# POVBase.net
KiCad netlist of a schematic drawn in EAGLE
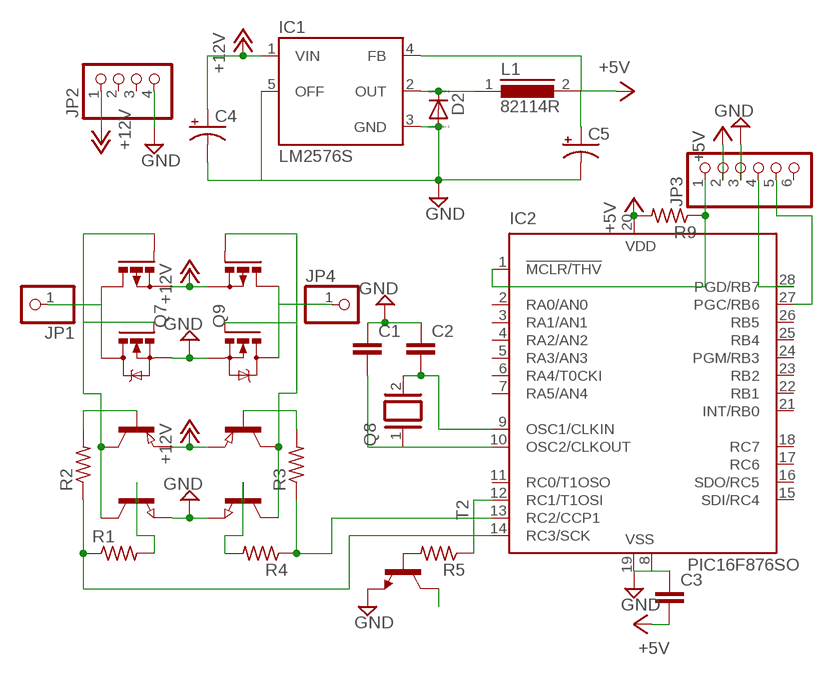
[diagram p0: schematic, sheet 1]

(export (version "E")
  (design (tool "Eeschema 10.0.6"))
  (components
    (comp (ref "C1")
      (value "C-EUC0805")
      (footprint "eagle-import:C0805")
      (libsource (lib "eagle-import") (part "C-EUC0805"))
    )
    (comp (ref "C2")
      (value "C-EUC0805")
      (footprint "eagle-import:C0805")
      (libsource (lib "eagle-import") (part "C-EUC0805"))
    )
    (comp (ref "C3")
      (value "C-EUC0805")
      (footprint "eagle-import:C0805")
      (libsource (lib "eagle-import") (part "C-EUC0805"))
    )
    (comp (ref "C4")
      (value "CPOL-USE2.5-7")
      (footprint "eagle-import:E2,5-7")
      (libsource (lib "eagle-import") (part "CPOL-USE2.5-7"))
    )
    (comp (ref "C5")
      (value "CPOL-USE1.8-4")
      (footprint "eagle-import:E1,8-4")
      (libsource (lib "eagle-import") (part "CPOL-USE1.8-4"))
    )
    (comp (ref "D2")
      (value "DIODE_E-SMC")
      (footprint "eagle-import:DIODE_SMC")
      (libsource (lib "eagle-import") (part "DIODE_E-SMC"))
    )
    (comp (ref "IC1")
      (value "LM2576S")
      (footprint "eagle-import:TO263-5")
      (libsource (lib "eagle-import") (part "LM2576S"))
    )
    (comp (ref "IC2")
      (value "PIC16F876SO")
      (footprint "eagle-import:SO28W")
      (fields (field (name "MF") "MICROCHIP") (field (name "MPN") "PIC16F876-20/SO"))
      (libsource (lib "eagle-import") (part "PIC16876SOF"))
    )
    (comp (ref "JP1")
      (value "PINHD-1X1")
      (footprint "eagle-import:1X01")
      (libsource (lib "eagle-import") (part "PINHD-1X1"))
    )
    (comp (ref "JP2")
      (value "PINHD-1X4")
      (footprint "eagle-import:1X04")
      (libsource (lib "eagle-import") (part "PINHD-1X4"))
    )
    (comp (ref "JP3")
      (value "PINHD-1X6")
      (footprint "eagle-import:1X06")
      (libsource (lib "eagle-import") (part "PINHD-1X6"))
    )
    (comp (ref "JP4")
      (value "PINHD-1X1")
      (footprint "eagle-import:1X01")
      (libsource (lib "eagle-import") (part "PINHD-1X1"))
    )
    (comp (ref "L1")
      (value "82114R")
      (footprint "eagle-import:82114R")
      (libsource (lib "eagle-import") (part "82114R"))
    )
    (comp (ref "Q1")
      (value "NPN-TRANSISTOR_SOT23")
      (footprint "eagle-import:SOT23")
      (libsource (lib "eagle-import") (part "NPN-TRANSISTOR_SOT23"))
    )
    (comp (ref "Q2")
      (value "NPN-TRANSISTOR_SOT23")
      (footprint "eagle-import:SOT23")
      (libsource (lib "eagle-import") (part "NPN-TRANSISTOR_SOT23"))
    )
    (comp (ref "Q3")
      (value "PNP-TRANSISTOR_SOT23")
      (footprint "eagle-import:SOT23")
      (libsource (lib "eagle-import") (part "PNP-TRANSISTOR_SOT23"))
    )
    (comp (ref "Q4")
      (value "PNP-TRANSISTOR_SOT23")
      (footprint "eagle-import:SOT23")
      (libsource (lib "eagle-import") (part "PNP-TRANSISTOR_SOT23"))
    )
    (comp (ref "Q5")
      (value "IRF540")
      (footprint "eagle-import:TO220BV")
      (libsource (lib "eagle-import") (part "IRF540"))
    )
    (comp (ref "Q6")
      (value "IRF540")
      (footprint "eagle-import:TO220BV")
      (libsource (lib "eagle-import") (part "IRF540"))
    )
    (comp (ref "Q7")
      (value "PMOSFET_PTO220BV")
      (footprint "eagle-import:TO220BV")
      (libsource (lib "eagle-import") (part "PMOSFET_PTO220BV"))
    )
    (comp (ref "Q8")
      (value "XTAL/S")
      (footprint "eagle-import:QS")
      (libsource (lib "eagle-import") (part "XTAL/S"))
    )
    (comp (ref "Q9")
      (value "PMOSFET_PTO220BV")
      (footprint "eagle-import:TO220BV")
      (libsource (lib "eagle-import") (part "PMOSFET_PTO220BV"))
    )
    (comp (ref "R1")
      (value "R-US_R0805")
      (footprint "eagle-import:R0805")
      (libsource (lib "eagle-import") (part "R-US_R0805"))
    )
    (comp (ref "R2")
      (value "R-US_R0805")
      (footprint "eagle-import:R0805")
      (libsource (lib "eagle-import") (part "R-US_R0805"))
    )
    (comp (ref "R3")
      (value "R-US_R0805")
      (footprint "eagle-import:R0805")
      (libsource (lib "eagle-import") (part "R-US_R0805"))
    )
    (comp (ref "R4")
      (value "R-US_R0805")
      (footprint "eagle-import:R0805")
      (libsource (lib "eagle-import") (part "R-US_R0805"))
    )
    (comp (ref "R5")
      (value "R-US_R0805")
      (footprint "eagle-import:R0805")
      (libsource (lib "eagle-import") (part "R-US_R0805"))
    )
    (comp (ref "R9")
      (value "R-US_R0805")
      (footprint "eagle-import:R0805")
      (libsource (lib "eagle-import") (part "R-US_R0805"))
    )
    (comp (ref "T2")
      (value "2SC1306")
      (footprint "eagle-import:TO220BV")
      (libsource (lib "eagle-import") (part "2SC1306"))
    )
  )
  (nets
    (net (code "1") (name "+5V") (class "Default")
      (node (ref "C3") (pin "2") (pinfunction "2_2") (pintype "passive"))
      (node (ref "C5") (pin "+") (pinfunction "+_+") (pintype "passive"))
      (node (ref "IC1") (pin "4") (pinfunction "FB_4") (pintype "input"))
      (node (ref "IC2") (pin "20") (pinfunction "VDD_20") (pintype "power_in"))
      (node (ref "JP3") (pin "2") (pinfunction "2_2") (pintype "passive"))
      (node (ref "L1") (pin "2") (pinfunction "2_2") (pintype "passive"))
      (node (ref "R9") (pin "2") (pinfunction "2_2") (pintype "passive"))
    )
    (net (code "2") (name "+12V") (class "Default")
      (node (ref "C4") (pin "+") (pinfunction "+_+") (pintype "passive"))
      (node (ref "IC1") (pin "1") (pinfunction "VIN_1") (pintype "power_in"))
      (node (ref "JP2") (pin "1") (pinfunction "1_1") (pintype "passive"))
      (node (ref "Q3") (pin "2") (pinfunction "E_2") (pintype "passive"))
      (node (ref "Q4") (pin "2") (pinfunction "E_2") (pintype "passive"))
      (node (ref "Q7") (pin "S") (pinfunction "S_S") (pintype "passive"))
      (node (ref "Q9") (pin "S") (pinfunction "S_S") (pintype "passive"))
    )
    (net (code "3") (name "GND") (class "Default")
      (node (ref "C1") (pin "1") (pinfunction "1_1") (pintype "passive"))
      (node (ref "C2") (pin "1") (pinfunction "1_1") (pintype "passive"))
      (node (ref "C3") (pin "1") (pinfunction "1_1") (pintype "passive"))
      (node (ref "C4") (pin "-") (pinfunction "-_-") (pintype "passive"))
      (node (ref "C5") (pin "-") (pinfunction "-_-") (pintype "passive"))
      (node (ref "D2") (pin "A") (pinfunction "C_A") (pintype "passive"))
      (node (ref "IC1") (pin "3") (pinfunction "GND_3") (pintype "power_in"))
      (node (ref "IC1") (pin "5") (pinfunction "OFF_5") (pintype "input"))
      (node (ref "IC2") (pin "19") (pinfunction "VSS_19") (pintype "power_in"))
      (node (ref "IC2") (pin "8") (pinfunction "VSS_8") (pintype "power_in"))
      (node (ref "JP2") (pin "4") (pinfunction "4_4") (pintype "passive"))
      (node (ref "JP3") (pin "3") (pinfunction "3_3") (pintype "passive"))
      (node (ref "Q1") (pin "2") (pinfunction "E_2") (pintype "passive"))
      (node (ref "Q2") (pin "2") (pinfunction "E_2") (pintype "passive"))
      (node (ref "Q5") (pin "S") (pinfunction "S_S") (pintype "passive"))
      (node (ref "Q6") (pin "S") (pinfunction "S_S") (pintype "passive"))
      (node (ref "T2") (pin "3") (pinfunction "E_3") (pintype "passive"))
    )
    (net (code "4") (name "Net-(D2-A)") (class "Default")
      (node (ref "D2") (pin "C") (pinfunction "A_C") (pintype "passive"))
      (node (ref "IC1") (pin "2") (pinfunction "OUT_2") (pintype "output"))
      (node (ref "L1") (pin "1") (pinfunction "1_1") (pintype "passive"))
    )
    (net (code "5") (name "Net-(IC2-OSC1{slash}CLKIN)") (class "Default")
      (node (ref "C2") (pin "2") (pinfunction "2_2") (pintype "passive"))
      (node (ref "IC2") (pin "9") (pinfunction "OSC1/CLKIN_9") (pintype "input"))
      (node (ref "Q8") (pin "2") (pinfunction "2_2") (pintype "passive"))
    )
    (net (code "6") (name "Net-(IC2-OSC2{slash}CLKOUT)") (class "Default")
      (node (ref "C1") (pin "2") (pinfunction "2_2") (pintype "passive"))
      (node (ref "IC2") (pin "10") (pinfunction "OSC2/CLKOUT_10") (pintype "output"))
      (node (ref "Q8") (pin "1") (pinfunction "1_1") (pintype "passive"))
    )
    (net (code "7") (name "Net-(IC2-PGC{slash}RB6)") (class "Default")
      (node (ref "IC2") (pin "27") (pinfunction "PGC/RB6_27") (pintype "bidirectional"))
      (node (ref "JP3") (pin "5") (pinfunction "5_5") (pintype "passive"))
    )
    (net (code "8") (name "Net-(IC2-PGD{slash}RB7)") (class "Default")
      (node (ref "IC2") (pin "28") (pinfunction "PGD/RB7_28") (pintype "bidirectional"))
      (node (ref "JP3") (pin "4") (pinfunction "4_4") (pintype "passive"))
    )
    (net (code "9") (name "Net-(IC2-RC1{slash}T1OSI)") (class "Default")
      (node (ref "IC2") (pin "12") (pinfunction "RC1/T1OSI_12") (pintype "bidirectional"))
      (node (ref "R5") (pin "1") (pinfunction "1_1") (pintype "passive"))
    )
    (net (code "10") (name "Net-(IC2-RC2{slash}CCP1)") (class "Default")
      (node (ref "IC2") (pin "13") (pinfunction "RC2/CCP1_13") (pintype "bidirectional"))
      (node (ref "R3") (pin "1") (pinfunction "1_1") (pintype "passive"))
      (node (ref "R4") (pin "1") (pinfunction "1_1") (pintype "passive"))
    )
    (net (code "11") (name "Net-(IC2-RC3{slash}SCK)") (class "Default")
      (node (ref "IC2") (pin "14") (pinfunction "RC3/SCK_14") (pintype "bidirectional"))
      (node (ref "R1") (pin "1") (pinfunction "1_1") (pintype "passive"))
      (node (ref "R2") (pin "1") (pinfunction "1_1") (pintype "passive"))
    )
    (net (code "12") (name "Net-(IC2-~{MCLR{slash}THV})") (class "Default")
      (node (ref "IC2") (pin "1") (pinfunction "~{MCLR/THV}_1") (pintype "input"))
      (node (ref "JP3") (pin "1") (pinfunction "1_1") (pintype "passive"))
      (node (ref "R9") (pin "1") (pinfunction "1_1") (pintype "passive"))
    )
    (net (code "13") (name "Net-(JP1-Pad1)") (class "Default")
      (node (ref "JP1") (pin "1") (pinfunction "1_1") (pintype "passive"))
      (node (ref "Q5") (pin "D") (pinfunction "D_D") (pintype "passive"))
      (node (ref "Q7") (pin "D") (pinfunction "D_D") (pintype "passive"))
    )
    (net (code "14") (name "Net-(JP4-Pad1)") (class "Default")
      (node (ref "JP4") (pin "1") (pinfunction "1_1") (pintype "passive"))
      (node (ref "Q6") (pin "D") (pinfunction "D_D") (pintype "passive"))
      (node (ref "Q9") (pin "D") (pinfunction "D_D") (pintype "passive"))
    )
    (net (code "15") (name "Net-(Q1-B)") (class "Default")
      (node (ref "Q1") (pin "1") (pinfunction "B_1") (pintype "passive"))
      (node (ref "R1") (pin "2") (pinfunction "2_2") (pintype "passive"))
    )
    (net (code "16") (name "Net-(Q1-C)") (class "Default")
      (node (ref "Q1") (pin "3") (pinfunction "C_3") (pintype "passive"))
      (node (ref "Q3") (pin "3") (pinfunction "C_3") (pintype "passive"))
      (node (ref "Q5") (pin "G") (pinfunction "G_G") (pintype "passive"))
      (node (ref "Q7") (pin "G") (pinfunction "G_G") (pintype "passive"))
    )
    (net (code "17") (name "Net-(Q2-B)") (class "Default")
      (node (ref "Q2") (pin "1") (pinfunction "B_1") (pintype "passive"))
      (node (ref "R4") (pin "2") (pinfunction "2_2") (pintype "passive"))
    )
    (net (code "18") (name "Net-(Q2-C)") (class "Default")
      (node (ref "Q2") (pin "3") (pinfunction "C_3") (pintype "passive"))
      (node (ref "Q4") (pin "3") (pinfunction "C_3") (pintype "passive"))
      (node (ref "Q6") (pin "G") (pinfunction "G_G") (pintype "passive"))
      (node (ref "Q9") (pin "G") (pinfunction "G_G") (pintype "passive"))
    )
    (net (code "19") (name "Net-(Q3-B)") (class "Default")
      (node (ref "Q3") (pin "1") (pinfunction "B_1") (pintype "passive"))
      (node (ref "R2") (pin "2") (pinfunction "2_2") (pintype "passive"))
    )
    (net (code "20") (name "Net-(Q4-B)") (class "Default")
      (node (ref "Q4") (pin "1") (pinfunction "B_1") (pintype "passive"))
      (node (ref "R3") (pin "2") (pinfunction "2_2") (pintype "passive"))
    )
    (net (code "21") (name "Net-(T2-B)") (class "Default")
      (node (ref "R5") (pin "2") (pinfunction "2_2") (pintype "passive"))
      (node (ref "T2") (pin "1") (pinfunction "B_1") (pintype "passive"))
    )
    (net (code "22") (name "unconnected-(IC2-INT{slash}RB0-Pad21)") (class "Default")
      (node (ref "IC2") (pin "21") (pinfunction "INT/RB0_21") (pintype "bidirectional"))
    )
    (net (code "23") (name "unconnected-(IC2-PGM{slash}RB3-Pad24)") (class "Default")
      (node (ref "IC2") (pin "24") (pinfunction "PGM/RB3_24") (pintype "bidirectional"))
    )
    (net (code "24") (name "unconnected-(IC2-RA0{slash}AN0-Pad2)") (class "Default")
      (node (ref "IC2") (pin "2") (pinfunction "RA0/AN0_2") (pintype "bidirectional"))
    )
    (net (code "25") (name "unconnected-(IC2-RA1{slash}AN1-Pad3)") (class "Default")
      (node (ref "IC2") (pin "3") (pinfunction "RA1/AN1_3") (pintype "bidirectional"))
    )
    (net (code "26") (name "unconnected-(IC2-RA2{slash}AN2-Pad4)") (class "Default")
      (node (ref "IC2") (pin "4") (pinfunction "RA2/AN2_4") (pintype "bidirectional"))
    )
    (net (code "27") (name "unconnected-(IC2-RA3{slash}AN3-Pad5)") (class "Default")
      (node (ref "IC2") (pin "5") (pinfunction "RA3/AN3_5") (pintype "bidirectional"))
    )
    (net (code "28") (name "unconnected-(IC2-RA4{slash}T0CKI-Pad6)") (class "Default")
      (node (ref "IC2") (pin "6") (pinfunction "RA4/T0CKI_6") (pintype "bidirectional"))
    )
    (net (code "29") (name "unconnected-(IC2-RA5{slash}AN4-Pad7)") (class "Default")
      (node (ref "IC2") (pin "7") (pinfunction "RA5/AN4_7") (pintype "bidirectional"))
    )
    (net (code "30") (name "unconnected-(IC2-RB1-Pad22)") (class "Default")
      (node (ref "IC2") (pin "22") (pinfunction "RB1_22") (pintype "bidirectional"))
    )
    (net (code "31") (name "unconnected-(IC2-RB2-Pad23)") (class "Default")
      (node (ref "IC2") (pin "23") (pinfunction "RB2_23") (pintype "bidirectional"))
    )
    (net (code "32") (name "unconnected-(IC2-RB4-Pad25)") (class "Default")
      (node (ref "IC2") (pin "25") (pinfunction "RB4_25") (pintype "bidirectional"))
    )
    (net (code "33") (name "unconnected-(IC2-RB5-Pad26)") (class "Default")
      (node (ref "IC2") (pin "26") (pinfunction "RB5_26") (pintype "bidirectional"))
    )
    (net (code "34") (name "unconnected-(IC2-RC0{slash}T1OSO-Pad11)") (class "Default")
      (node (ref "IC2") (pin "11") (pinfunction "RC0/T1OSO_11") (pintype "bidirectional"))
    )
    (net (code "35") (name "unconnected-(IC2-RC6-Pad17)") (class "Default")
      (node (ref "IC2") (pin "17") (pinfunction "RC6_17") (pintype "bidirectional"))
    )
    (net (code "36") (name "unconnected-(IC2-RC7-Pad18)") (class "Default")
      (node (ref "IC2") (pin "18") (pinfunction "RC7_18") (pintype "bidirectional"))
    )
    (net (code "37") (name "unconnected-(IC2-SDI{slash}RC4-Pad15)") (class "Default")
      (node (ref "IC2") (pin "15") (pinfunction "SDI/RC4_15") (pintype "bidirectional"))
    )
    (net (code "38") (name "unconnected-(IC2-SDO{slash}RC5-Pad16)") (class "Default")
      (node (ref "IC2") (pin "16") (pinfunction "SDO/RC5_16") (pintype "bidirectional"))
    )
    (net (code "39") (name "unconnected-(JP2-Pad2)") (class "Default")
      (node (ref "JP2") (pin "2") (pinfunction "2_2") (pintype "passive"))
    )
    (net (code "40") (name "unconnected-(JP2-Pad3)") (class "Default")
      (node (ref "JP2") (pin "3") (pinfunction "3_3") (pintype "passive"))
    )
    (net (code "41") (name "unconnected-(JP3-Pad6)") (class "Default")
      (node (ref "JP3") (pin "6") (pinfunction "6_6") (pintype "passive"))
    )
    (net (code "42") (name "unconnected-(T2-C-Pad2)") (class "Default")
      (node (ref "T2") (pin "2") (pinfunction "C_2") (pintype "passive"))
    )
  )
)
